# HMC580.net
KiCad netlist of a schematic drawn in Altium Designer
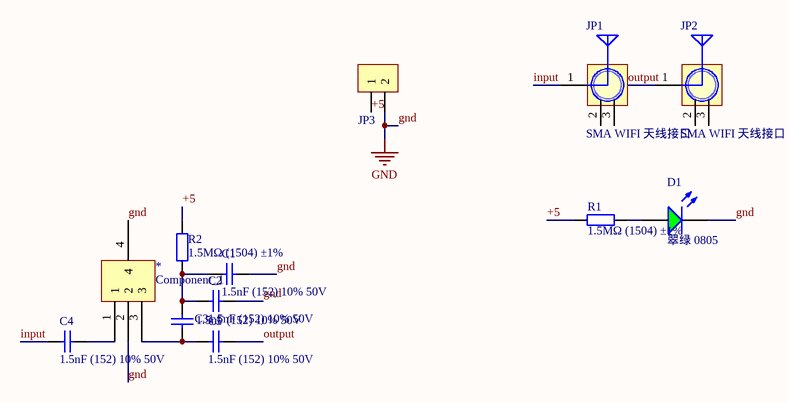
[diagram p0: 射频功放HMC580.SchDoc]

(export (version "E")
  (design (tool "Eeschema 10.0.6"))
  (components
    (comp (ref "*")
      (value "Component_1")
      (footprint "SOT89_N")
      (libsource (lib "Schlib2") (part "Component_1"))
    )
    (comp (ref "C1")
      (value "1.5nF (152) 10% 50V")
      (footprint "0805_C")
      (description "贴片电容")
      (libsource (lib "Miscellaneous Devices LC") (part "0805 1.5nF (152) 10% 50V"))
    )
    (comp (ref "C2")
      (value "1.5nF (152) 10% 50V")
      (footprint "0805_C")
      (description "贴片电容")
      (libsource (lib "Miscellaneous Devices LC") (part "0805 1.5nF (152) 10% 50V"))
    )
    (comp (ref "C3")
      (value "1.5nF (152) 10% 50V")
      (footprint "0805_C")
      (description "贴片电容")
      (libsource (lib "Miscellaneous Devices LC") (part "0805 1.5nF (152) 10% 50V"))
    )
    (comp (ref "C4")
      (value "1.5nF (152) 10% 50V")
      (footprint "0805_C")
      (description "贴片电容")
      (libsource (lib "Miscellaneous Devices LC") (part "0805 1.5nF (152) 10% 50V"))
    )
    (comp (ref "C5")
      (value "1.5nF (152) 10% 50V")
      (footprint "0805_C")
      (description "贴片电容")
      (libsource (lib "Miscellaneous Devices LC") (part "0805 1.5nF (152) 10% 50V"))
    )
    (comp (ref "D1")
      (value "翠绿 0805")
      (footprint "0805_LED_S1")
      (description "发光二极管")
      (libsource (lib "Miscellaneous Devices LC") (part "0805 翠绿"))
    )
    (comp (ref "JP1")
      (value "SMA WIFI 天线接口")
      (footprint "SMA-KE")
      (description "SMA-2.4G射频天线接口")
      (libsource (lib "天线") (part "SMA"))
    )
    (comp (ref "JP2")
      (value "SMA WIFI 天线接口")
      (footprint "SMA-KE")
      (description "SMA-2.4G射频天线接口")
      (libsource (lib "天线") (part "SMA"))
    )
    (comp (ref "JP3")
      (value "HDR-1X2")
      (footprint "XH2.54-LI-2P")
      (description "2P接插件")
      (libsource (lib "XH2.54") (part "Header 2"))
    )
    (comp (ref "R1")
      (value "1.5MΩ (1504) ±1%")
      (footprint "0805_R")
      (description "贴片电阻")
      (libsource (lib "Miscellaneous Devices LC") (part "0805 1.5MΩ (1504) 1%"))
    )
    (comp (ref "R2")
      (value "1.5MΩ (1504) ±1%")
      (footprint "0805_R")
      (description "贴片电阻")
      (libsource (lib "") (part "0805 1.5MΩ (1504) 1%_1"))
    )
  )
  (nets
    (net (code "1") (name "/+5") (class "Default")
      (node (ref "JP3") (pin "1") (pinfunction "1_1") (pintype "passive"))
      (node (ref "R1") (pin "1") (pinfunction "1_1") (pintype "passive"))
      (node (ref "R2") (pin "2") (pinfunction "2_2") (pintype "passive"))
    )
    (net (code "2") (name "/input") (class "Default")
      (node (ref "C4") (pin "2") (pinfunction "2_2") (pintype "passive"))
      (node (ref "JP1") (pin "1") (pinfunction "ANT_1") (pintype "passive"))
    )
    (net (code "3") (name "/output") (class "Default")
      (node (ref "C5") (pin "1") (pinfunction "1_1") (pintype "passive"))
      (node (ref "JP2") (pin "1") (pinfunction "ANT_1") (pintype "passive"))
    )
    (net (code "4") (name "GND") (class "Default")
      (node (ref "*") (pin "2") (pinfunction "2_2") (pintype "passive"))
      (node (ref "*") (pin "4") (pinfunction "4_4") (pintype "passive"))
      (node (ref "C1") (pin "1") (pinfunction "1_1") (pintype "passive"))
      (node (ref "C2") (pin "1") (pinfunction "1_1") (pintype "passive"))
      (node (ref "D1") (pin "K") (pinfunction "K_K") (pintype "passive"))
      (node (ref "JP3") (pin "2") (pinfunction "2_2") (pintype "passive"))
    )
    (net (code "5") (name "Net-(*-Pad1)") (class "Default")
      (node (ref "*") (pin "1") (pinfunction "1_1") (pintype "passive"))
      (node (ref "C4") (pin "1") (pinfunction "1_1") (pintype "passive"))
    )
    (net (code "6") (name "Net-(*-Pad3)") (class "Default")
      (node (ref "*") (pin "3") (pinfunction "3_3") (pintype "passive"))
      (node (ref "C3") (pin "1") (pinfunction "1_1") (pintype "passive"))
      (node (ref "C5") (pin "2") (pinfunction "2_2") (pintype "passive"))
    )
    (net (code "7") (name "Net-(C1-Pad2)") (class "Default")
      (node (ref "C1") (pin "2") (pinfunction "2_2") (pintype "passive"))
      (node (ref "C2") (pin "2") (pinfunction "2_2") (pintype "passive"))
      (node (ref "C3") (pin "2") (pinfunction "2_2") (pintype "passive"))
      (node (ref "R2") (pin "1") (pinfunction "1_1") (pintype "passive"))
    )
    (net (code "8") (name "Net-(D1-PadA)") (class "Default")
      (node (ref "D1") (pin "A") (pinfunction "A_A") (pintype "passive"))
      (node (ref "R1") (pin "2") (pinfunction "2_2") (pintype "passive"))
    )
    (net (code "9") (name "unconnected-(JP1-GND-Pad2)") (class "Default")
      (node (ref "JP1") (pin "2") (pinfunction "GND_2") (pintype "passive"))
    )
    (net (code "10") (name "unconnected-(JP1-GND-Pad3)") (class "Default")
      (node (ref "JP1") (pin "3") (pinfunction "GND_3") (pintype "passive"))
    )
    (net (code "11") (name "unconnected-(JP2-GND-Pad2)") (class "Default")
      (node (ref "JP2") (pin "2") (pinfunction "GND_2") (pintype "passive"))
    )
    (net (code "12") (name "unconnected-(JP2-GND-Pad3)") (class "Default")
      (node (ref "JP2") (pin "3") (pinfunction "GND_3") (pintype "passive"))
    )
  )
)
